# wts_transmitter.net
KiCad netlist of a schematic drawn in EAGLE
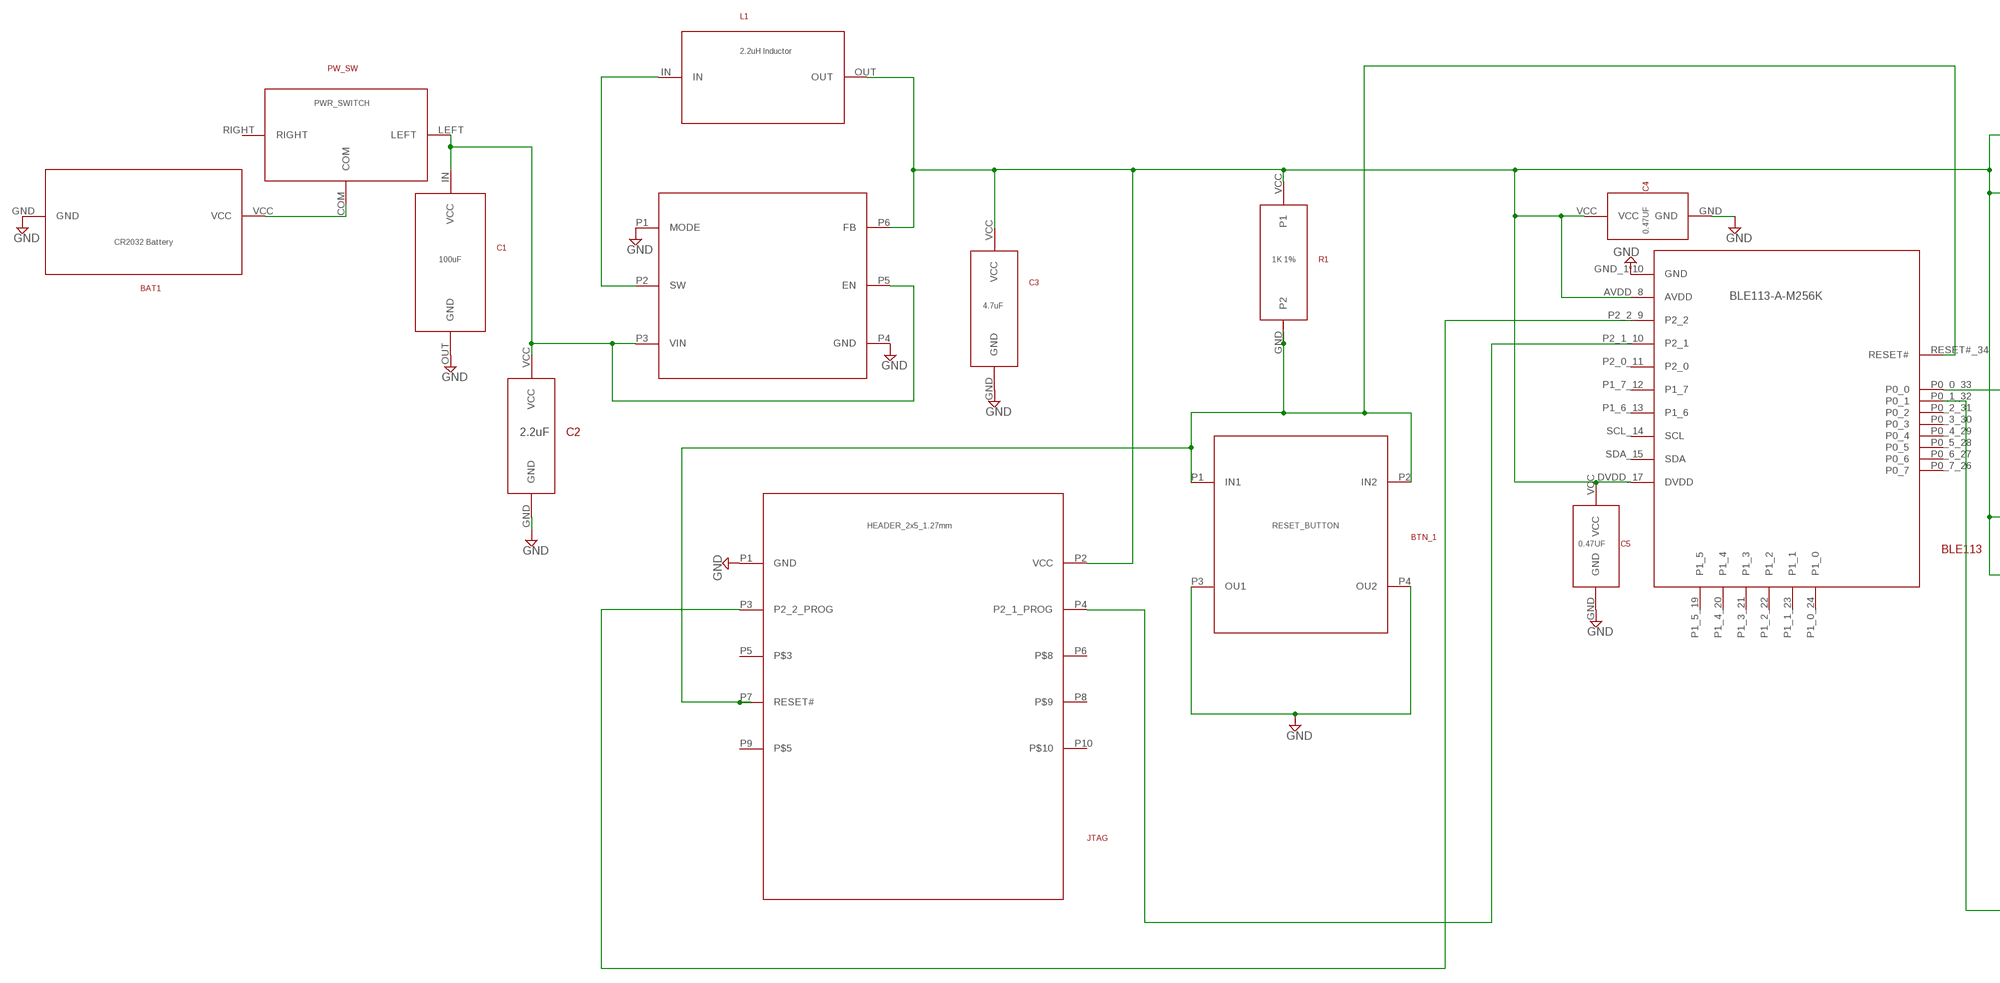
[diagram p0: schematic, sheet 1, part 1 of 2]
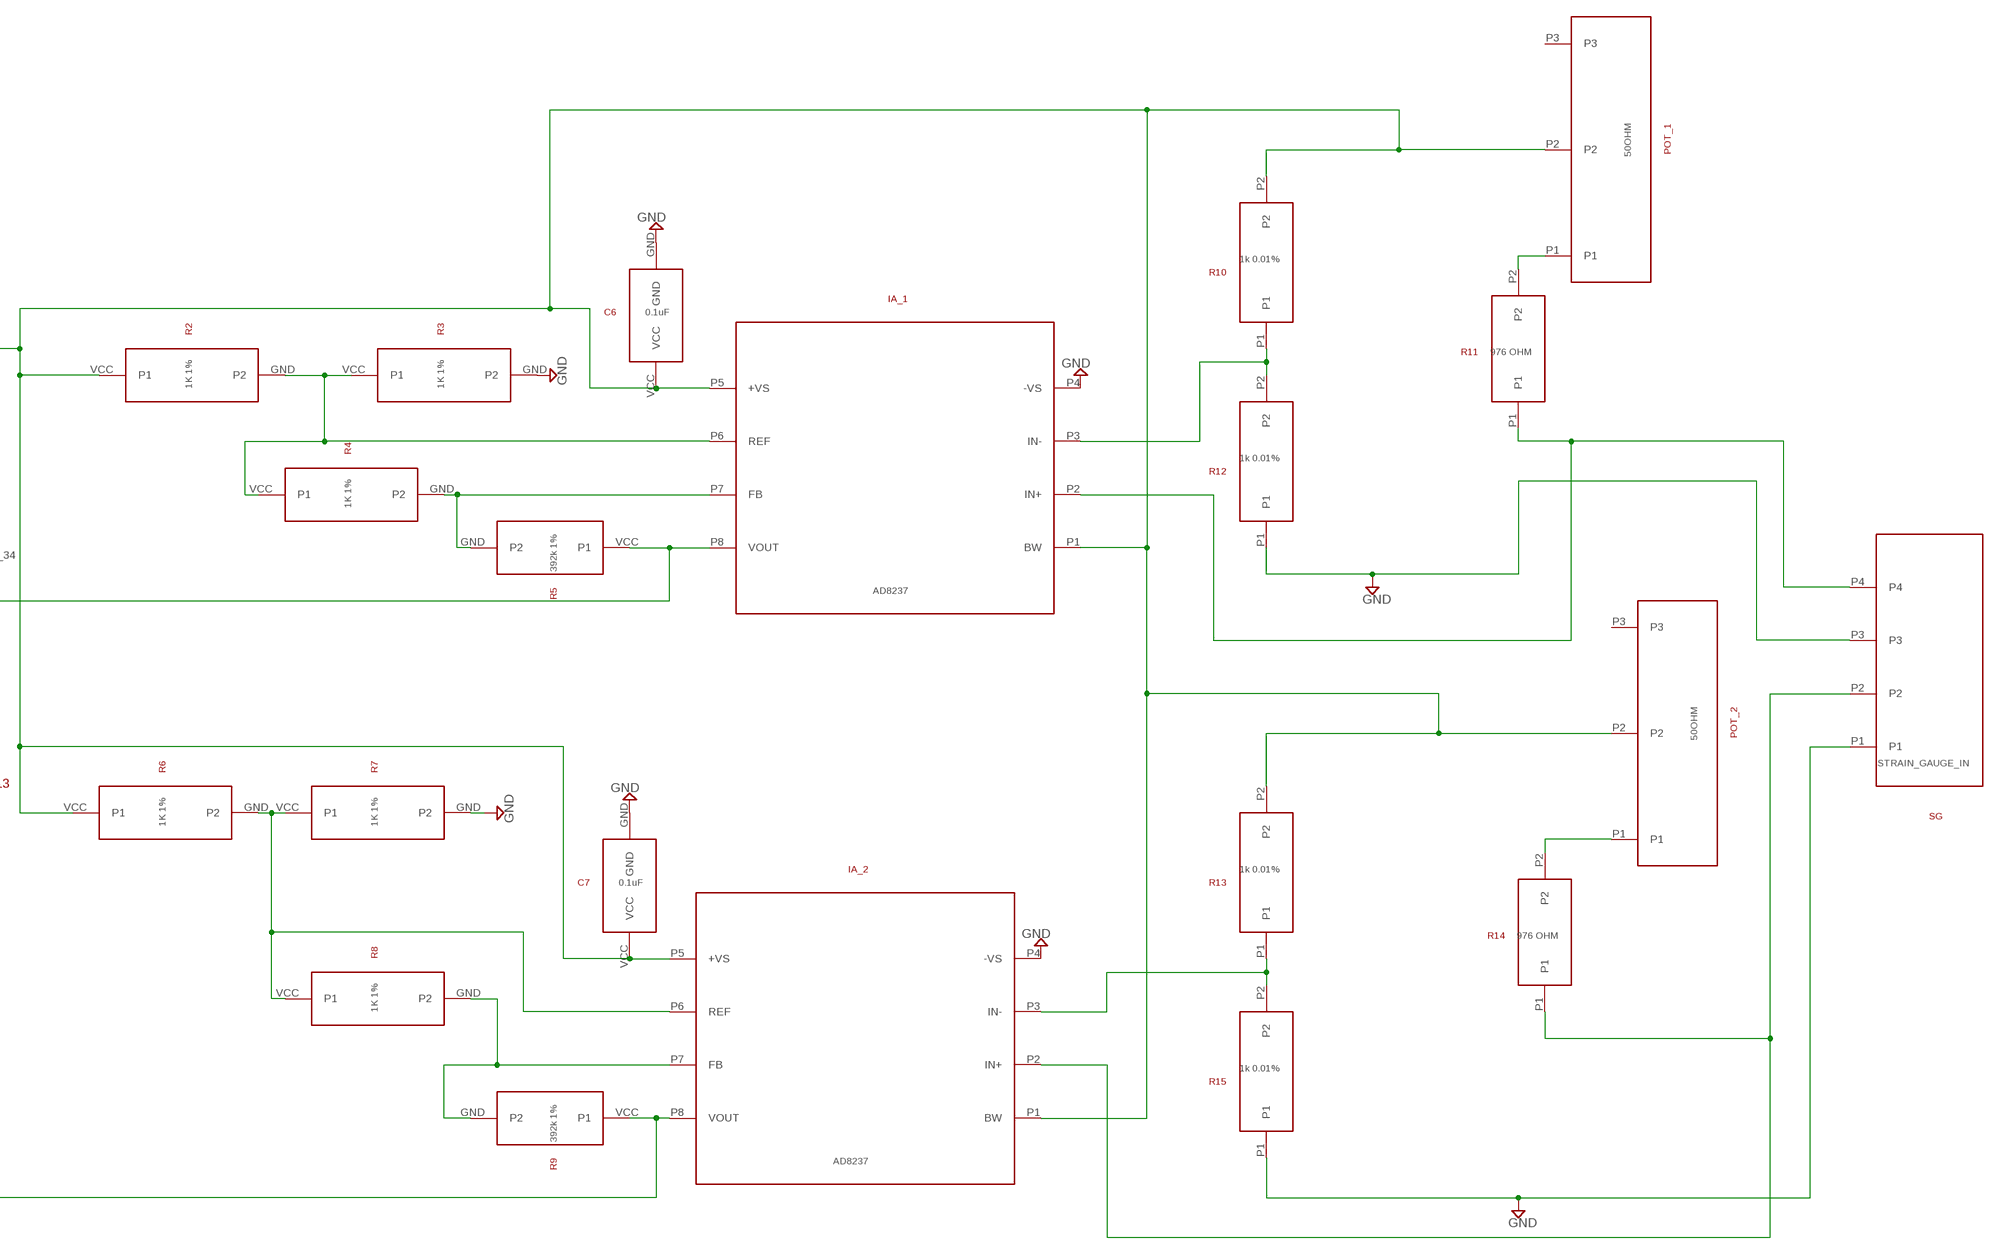
[diagram p1: schematic, sheet 1, part 2 of 2]

(export (version "E")
  (design (tool "Eeschema 10.0.6"))
  (components
    (comp (ref "BAT1")
      (value "CR2032")
      (footprint "eagle-import:CR2032")
      (libsource (lib "eagle-import") (part "CR2032"))
    )
    (comp (ref "BLE113")
      (value "BLE113-A-M256K")
      (footprint "eagle-import:BLE113")
      (libsource (lib "eagle-import") (part "BLE113-A-M256K"))
    )
    (comp (ref "BTN_1")
      (value "RESET_BUTTON")
      (footprint "eagle-import:RESET_SMT")
      (libsource (lib "eagle-import") (part "RESET_BUTTON"))
    )
    (comp (ref "C1")
      (value "100UF_CAP")
      (footprint "eagle-import:1206")
      (libsource (lib "eagle-import") (part "100UF_CAP"))
    )
    (comp (ref "C2")
      (value "2.2UF_CAP")
      (footprint "eagle-import:0603")
      (libsource (lib "eagle-import") (part "2.2UF_CAP"))
    )
    (comp (ref "C3")
      (value "4.7UF_CAP")
      (footprint "eagle-import:0603")
      (libsource (lib "eagle-import") (part "4.7UF_CAP"))
    )
    (comp (ref "C4")
      (value "0.47UF_CAP")
      (footprint "eagle-import:0402")
      (libsource (lib "eagle-import") (part "0.47UF_CAP"))
    )
    (comp (ref "C5")
      (value "0.47UF_CAP")
      (footprint "eagle-import:0402")
      (libsource (lib "eagle-import") (part "0.47UF_CAP"))
    )
    (comp (ref "C6")
      (value "0.1UF_CAP")
      (footprint "eagle-import:0402")
      (libsource (lib "eagle-import") (part "0.1UF_CAP"))
    )
    (comp (ref "C7")
      (value "0.1UF_CAP")
      (footprint "eagle-import:0402")
      (libsource (lib "eagle-import") (part "0.1UF_CAP"))
    )
    (comp (ref "DC_DC")
      (value "TPS62234")
      (footprint "eagle-import:DRY6")
      (libsource (lib "eagle-import") (part "TPS62234"))
    )
    (comp (ref "IA_1")
      (value "AD8237")
      (footprint "eagle-import:MSOP8")
      (libsource (lib "eagle-import") (part "AD8237"))
    )
    (comp (ref "IA_2")
      (value "AD8237")
      (footprint "eagle-import:MSOP8")
      (libsource (lib "eagle-import") (part "AD8237"))
    )
    (comp (ref "JTAG")
      (value "JTAG_HEADER")
      (footprint "eagle-import:1.27MM_2X5_HEADER")
      (libsource (lib "eagle-import") (part "JTAG_HEADER"))
    )
    (comp (ref "L1")
      (value "2.2UH_INDUCTOR")
      (footprint "eagle-import:1206")
      (libsource (lib "eagle-import") (part "2.2UH_INDUCTOR"))
    )
    (comp (ref "POT_1")
      (value "50OHM_TRIMPOT")
      (footprint "eagle-import:PV36W_TRIMPOT")
      (libsource (lib "eagle-import") (part "50OHM_TRIMPOT"))
    )
    (comp (ref "POT_2")
      (value "50OHM_TRIMPOT")
      (footprint "eagle-import:PV36W_TRIMPOT")
      (libsource (lib "eagle-import") (part "50OHM_TRIMPOT"))
    )
    (comp (ref "PW_SW")
      (value "PWR_SWITCH")
      (footprint "eagle-import:PWR_SWITCH")
      (libsource (lib "eagle-import") (part "PWR_SWITCH"))
    )
    (comp (ref "R1")
      (value "1KOHM_RESISTOR_1%")
      (footprint "eagle-import:0603")
      (libsource (lib "eagle-import") (part "1KOHM_RESISTOR_1%"))
    )
    (comp (ref "R2")
      (value "1KOHM_RESISTOR_1%")
      (footprint "eagle-import:0603")
      (libsource (lib "eagle-import") (part "1KOHM_RESISTOR_1%"))
    )
    (comp (ref "R3")
      (value "1KOHM_RESISTOR_1%")
      (footprint "eagle-import:0603")
      (libsource (lib "eagle-import") (part "1KOHM_RESISTOR_1%"))
    )
    (comp (ref "R4")
      (value "1KOHM_RESISTOR_1%")
      (footprint "eagle-import:0603")
      (libsource (lib "eagle-import") (part "1KOHM_RESISTOR_1%"))
    )
    (comp (ref "R5")
      (value "392KOHM_RESISTOR_1%")
      (footprint "eagle-import:0603")
      (libsource (lib "eagle-import") (part "392KOHM_RESISTOR_1%"))
    )
    (comp (ref "R6")
      (value "1KOHM_RESISTOR_1%")
      (footprint "eagle-import:0603")
      (libsource (lib "eagle-import") (part "1KOHM_RESISTOR_1%"))
    )
    (comp (ref "R7")
      (value "1KOHM_RESISTOR_1%")
      (footprint "eagle-import:0603")
      (libsource (lib "eagle-import") (part "1KOHM_RESISTOR_1%"))
    )
    (comp (ref "R8")
      (value "1KOHM_RESISTOR_1%")
      (footprint "eagle-import:0603")
      (libsource (lib "eagle-import") (part "1KOHM_RESISTOR_1%"))
    )
    (comp (ref "R9")
      (value "392KOHM_RESISTOR_1%")
      (footprint "eagle-import:0603")
      (libsource (lib "eagle-import") (part "392KOHM_RESISTOR_1%"))
    )
    (comp (ref "R10")
      (value "1KOHM_RESISTOR_0.01%")
      (footprint "eagle-import:0805")
      (libsource (lib "eagle-import") (part "1KOHM_RESISTOR_0.01%"))
    )
    (comp (ref "R11")
      (value "976OHM_RESISTOR")
      (footprint "eagle-import:0805")
      (libsource (lib "eagle-import") (part "976OHM_RESISTOR"))
    )
    (comp (ref "R12")
      (value "1KOHM_RESISTOR_0.01%")
      (footprint "eagle-import:0805")
      (libsource (lib "eagle-import") (part "1KOHM_RESISTOR_0.01%"))
    )
    (comp (ref "R13")
      (value "1KOHM_RESISTOR_0.01%")
      (footprint "eagle-import:0805")
      (libsource (lib "eagle-import") (part "1KOHM_RESISTOR_0.01%"))
    )
    (comp (ref "R14")
      (value "976OHM_RESISTOR")
      (footprint "eagle-import:0805")
      (libsource (lib "eagle-import") (part "976OHM_RESISTOR"))
    )
    (comp (ref "R15")
      (value "1KOHM_RESISTOR_0.01%")
      (footprint "eagle-import:0805")
      (libsource (lib "eagle-import") (part "1KOHM_RESISTOR_0.01%"))
    )
    (comp (ref "SG")
      (value "4_PIN_5.08MM_TERMINAL")
      (footprint "eagle-import:5.08MM_4PIN_HEADER")
      (libsource (lib "eagle-import") (part "4_PIN_5.08MM_TERMINAL"))
    )
  )
  (nets
    (net (code "1") (name "GND") (class "Default")
      (node (ref "BAT1") (pin "GND") (pinfunction "GND_GND") (pintype "power_in"))
      (node (ref "BLE113") (pin "GND_1") (pinfunction "GND_GND_1") (pintype "power_in"))
      (node (ref "BLE113") (pin "GND_18") (pinfunction "GND_GND_18") (pintype "power_in"))
      (node (ref "BLE113") (pin "GND_2") (pinfunction "GND_GND_2") (pintype "power_in"))
      (node (ref "BLE113") (pin "GND_25") (pinfunction "GND_GND_25") (pintype "power_in"))
      (node (ref "BLE113") (pin "GND_3") (pinfunction "GND_GND_3") (pintype "power_in"))
      (node (ref "BLE113") (pin "GND_36") (pinfunction "GND_GND_36") (pintype "power_in"))
      (node (ref "BLE113") (pin "GND_4") (pinfunction "GND_GND_4") (pintype "power_in"))
      (node (ref "BLE113") (pin "GND_5") (pinfunction "GND_GND_5") (pintype "power_in"))
      (node (ref "BLE113") (pin "GND_6") (pinfunction "GND_GND_6") (pintype "power_in"))
      (node (ref "BLE113") (pin "GND_7") (pinfunction "GND_GND_7") (pintype "power_in"))
      (node (ref "BTN_1") (pin "P3") (pinfunction "OU1_P3") (pintype "bidirectional"))
      (node (ref "BTN_1") (pin "P4") (pinfunction "OU2_P4") (pintype "bidirectional"))
      (node (ref "C1") (pin "OUT") (pinfunction "GND_OUT") (pintype "power_in"))
      (node (ref "C2") (pin "GND") (pinfunction "GND_GND") (pintype "power_in"))
      (node (ref "C3") (pin "GND") (pinfunction "GND_GND") (pintype "bidirectional"))
      (node (ref "C4") (pin "GND") (pinfunction "GND_GND") (pintype "power_in"))
      (node (ref "C5") (pin "GND") (pinfunction "GND_GND") (pintype "power_in"))
      (node (ref "C6") (pin "GND") (pinfunction "GND_GND") (pintype "bidirectional"))
      (node (ref "C7") (pin "GND") (pinfunction "GND_GND") (pintype "bidirectional"))
      (node (ref "DC_DC") (pin "P1") (pinfunction "MODE_P1") (pintype "input"))
      (node (ref "DC_DC") (pin "P4") (pinfunction "GND_P4") (pintype "power_in"))
      (node (ref "IA_1") (pin "P4") (pinfunction "-VS_P4") (pintype "bidirectional"))
      (node (ref "IA_2") (pin "P4") (pinfunction "-VS_P4") (pintype "bidirectional"))
      (node (ref "JTAG") (pin "P1") (pinfunction "GND_P1") (pintype "bidirectional"))
      (node (ref "R12") (pin "P1") (pinfunction "P1_P1") (pintype "bidirectional"))
      (node (ref "R15") (pin "P1") (pinfunction "P1_P1") (pintype "bidirectional"))
      (node (ref "R3") (pin "GND") (pinfunction "P2_GND") (pintype "bidirectional"))
      (node (ref "R7") (pin "GND") (pinfunction "P2_GND") (pintype "bidirectional"))
      (node (ref "SG") (pin "P1") (pinfunction "P1_P1") (pintype "bidirectional"))
      (node (ref "SG") (pin "P3") (pinfunction "P3_P3") (pintype "bidirectional"))
    )
    (net (code "2") (name "Net-(BAT1-PadVCC)") (class "Default")
      (node (ref "BAT1") (pin "VCC") (pinfunction "VCC_VCC") (pintype "power_in"))
      (node (ref "PW_SW") (pin "COM") (pinfunction "COM_COM") (pintype "bidirectional"))
    )
    (net (code "3") (name "Net-(BLE113-AVDD)") (class "Default")
      (node (ref "BLE113") (pin "AVDD_8") (pinfunction "AVDD_AVDD_8") (pintype "power_in"))
      (node (ref "BLE113") (pin "DVDD_17") (pinfunction "DVDD_DVDD_17") (pintype "power_in"))
      (node (ref "C3") (pin "VCC") (pinfunction "VCC_VCC") (pintype "bidirectional"))
      (node (ref "C4") (pin "VCC") (pinfunction "VCC_VCC") (pintype "power_in"))
      (node (ref "C5") (pin "VCC") (pinfunction "VCC_VCC") (pintype "power_in"))
      (node (ref "C6") (pin "VCC") (pinfunction "VCC_VCC") (pintype "bidirectional"))
      (node (ref "C7") (pin "VCC") (pinfunction "VCC_VCC") (pintype "bidirectional"))
      (node (ref "DC_DC") (pin "P6") (pinfunction "FB_P6") (pintype "input"))
      (node (ref "IA_1") (pin "P1") (pinfunction "BW_P1") (pintype "bidirectional"))
      (node (ref "IA_1") (pin "P5") (pinfunction "+VS_P5") (pintype "bidirectional"))
      (node (ref "IA_2") (pin "P1") (pinfunction "BW_P1") (pintype "bidirectional"))
      (node (ref "IA_2") (pin "P5") (pinfunction "+VS_P5") (pintype "bidirectional"))
      (node (ref "JTAG") (pin "P2") (pinfunction "VCC_P2") (pintype "bidirectional"))
      (node (ref "L1") (pin "OUT") (pinfunction "OUT_OUT") (pintype "bidirectional"))
      (node (ref "POT_1") (pin "P2") (pinfunction "P2_P2") (pintype "bidirectional"))
      (node (ref "POT_2") (pin "P2") (pinfunction "P2_P2") (pintype "bidirectional"))
      (node (ref "R1") (pin "VCC") (pinfunction "P1_VCC") (pintype "bidirectional"))
      (node (ref "R10") (pin "P2") (pinfunction "P2_P2") (pintype "bidirectional"))
      (node (ref "R13") (pin "P2") (pinfunction "P2_P2") (pintype "bidirectional"))
      (node (ref "R2") (pin "VCC") (pinfunction "P1_VCC") (pintype "bidirectional"))
      (node (ref "R6") (pin "VCC") (pinfunction "P1_VCC") (pintype "bidirectional"))
    )
    (net (code "4") (name "Net-(BLE113-P0_0)") (class "Default")
      (node (ref "BLE113") (pin "P0_0_33") (pinfunction "P0_0_P0_0_33") (pintype "bidirectional"))
      (node (ref "IA_1") (pin "P8") (pinfunction "VOUT_P8") (pintype "bidirectional"))
      (node (ref "R5") (pin "VCC") (pinfunction "P1_VCC") (pintype "bidirectional"))
    )
    (net (code "5") (name "Net-(BLE113-P0_1)") (class "Default")
      (node (ref "BLE113") (pin "P0_1_32") (pinfunction "P0_1_P0_1_32") (pintype "bidirectional"))
      (node (ref "IA_2") (pin "P8") (pinfunction "VOUT_P8") (pintype "bidirectional"))
      (node (ref "R9") (pin "VCC") (pinfunction "P1_VCC") (pintype "bidirectional"))
    )
    (net (code "6") (name "Net-(BLE113-P2_1)") (class "Default")
      (node (ref "BLE113") (pin "P2_1_10") (pinfunction "P2_1_P2_1_10") (pintype "bidirectional"))
      (node (ref "JTAG") (pin "P4") (pinfunction "P2_1_PROG_P4") (pintype "bidirectional"))
    )
    (net (code "7") (name "Net-(BLE113-P2_2)") (class "Default")
      (node (ref "BLE113") (pin "P2_2_9") (pinfunction "P2_2_P2_2_9") (pintype "bidirectional"))
      (node (ref "JTAG") (pin "P3") (pinfunction "P2_2_PROG_P3") (pintype "bidirectional"))
    )
    (net (code "8") (name "Net-(BLE113-RESET#)") (class "Default")
      (node (ref "BLE113") (pin "RESET#_34") (pinfunction "RESET#_RESET#_34") (pintype "input"))
      (node (ref "BTN_1") (pin "P1") (pinfunction "IN1_P1") (pintype "bidirectional"))
      (node (ref "BTN_1") (pin "P2") (pinfunction "IN2_P2") (pintype "bidirectional"))
      (node (ref "JTAG") (pin "P7") (pinfunction "RESET#_P7") (pintype "bidirectional"))
      (node (ref "R1") (pin "GND") (pinfunction "P2_GND") (pintype "bidirectional"))
    )
    (net (code "9") (name "Net-(C1-VCC)") (class "Default")
      (node (ref "C1") (pin "IN") (pinfunction "VCC_IN") (pintype "power_in"))
      (node (ref "C2") (pin "VCC") (pinfunction "VCC_VCC") (pintype "power_in"))
      (node (ref "DC_DC") (pin "P3") (pinfunction "VIN_P3") (pintype "power_in"))
      (node (ref "DC_DC") (pin "P5") (pinfunction "EN_P5") (pintype "input"))
      (node (ref "PW_SW") (pin "LEFT") (pinfunction "LEFT_LEFT") (pintype "bidirectional"))
    )
    (net (code "10") (name "Net-(DC_DC-SW)") (class "Default")
      (node (ref "DC_DC") (pin "P2") (pinfunction "SW_P2") (pintype "output"))
      (node (ref "L1") (pin "IN") (pinfunction "IN_IN") (pintype "bidirectional"))
    )
    (net (code "11") (name "Net-(IA_1-FB)") (class "Default")
      (node (ref "IA_1") (pin "P7") (pinfunction "FB_P7") (pintype "bidirectional"))
      (node (ref "R4") (pin "GND") (pinfunction "P2_GND") (pintype "bidirectional"))
      (node (ref "R5") (pin "GND") (pinfunction "P2_GND") (pintype "bidirectional"))
    )
    (net (code "12") (name "Net-(IA_1-IN+)") (class "Default")
      (node (ref "IA_1") (pin "P2") (pinfunction "IN+_P2") (pintype "bidirectional"))
      (node (ref "R11") (pin "P1") (pinfunction "P1_P1") (pintype "bidirectional"))
      (node (ref "SG") (pin "P4") (pinfunction "P4_P4") (pintype "bidirectional"))
    )
    (net (code "13") (name "Net-(IA_1-IN-)") (class "Default")
      (node (ref "IA_1") (pin "P3") (pinfunction "IN-_P3") (pintype "bidirectional"))
      (node (ref "R10") (pin "P1") (pinfunction "P1_P1") (pintype "bidirectional"))
      (node (ref "R12") (pin "P2") (pinfunction "P2_P2") (pintype "bidirectional"))
    )
    (net (code "14") (name "Net-(IA_1-REF)") (class "Default")
      (node (ref "IA_1") (pin "P6") (pinfunction "REF_P6") (pintype "bidirectional"))
      (node (ref "R2") (pin "GND") (pinfunction "P2_GND") (pintype "bidirectional"))
      (node (ref "R3") (pin "VCC") (pinfunction "P1_VCC") (pintype "bidirectional"))
      (node (ref "R4") (pin "VCC") (pinfunction "P1_VCC") (pintype "bidirectional"))
    )
    (net (code "15") (name "Net-(IA_2-FB)") (class "Default")
      (node (ref "IA_2") (pin "P7") (pinfunction "FB_P7") (pintype "bidirectional"))
      (node (ref "R8") (pin "GND") (pinfunction "P2_GND") (pintype "bidirectional"))
      (node (ref "R9") (pin "GND") (pinfunction "P2_GND") (pintype "bidirectional"))
    )
    (net (code "16") (name "Net-(IA_2-IN+)") (class "Default")
      (node (ref "IA_2") (pin "P2") (pinfunction "IN+_P2") (pintype "bidirectional"))
      (node (ref "R14") (pin "P1") (pinfunction "P1_P1") (pintype "bidirectional"))
      (node (ref "SG") (pin "P2") (pinfunction "P2_P2") (pintype "bidirectional"))
    )
    (net (code "17") (name "Net-(IA_2-IN-)") (class "Default")
      (node (ref "IA_2") (pin "P3") (pinfunction "IN-_P3") (pintype "bidirectional"))
      (node (ref "R13") (pin "P1") (pinfunction "P1_P1") (pintype "bidirectional"))
      (node (ref "R15") (pin "P2") (pinfunction "P2_P2") (pintype "bidirectional"))
    )
    (net (code "18") (name "Net-(IA_2-REF)") (class "Default")
      (node (ref "IA_2") (pin "P6") (pinfunction "REF_P6") (pintype "bidirectional"))
      (node (ref "R6") (pin "GND") (pinfunction "P2_GND") (pintype "bidirectional"))
      (node (ref "R7") (pin "VCC") (pinfunction "P1_VCC") (pintype "bidirectional"))
      (node (ref "R8") (pin "VCC") (pinfunction "P1_VCC") (pintype "bidirectional"))
    )
    (net (code "19") (name "Net-(POT_1-PadP1)") (class "Default")
      (node (ref "POT_1") (pin "P1") (pinfunction "P1_P1") (pintype "bidirectional"))
      (node (ref "R11") (pin "P2") (pinfunction "P2_P2") (pintype "bidirectional"))
    )
    (net (code "20") (name "Net-(POT_2-PadP1)") (class "Default")
      (node (ref "POT_2") (pin "P1") (pinfunction "P1_P1") (pintype "bidirectional"))
      (node (ref "R14") (pin "P2") (pinfunction "P2_P2") (pintype "bidirectional"))
    )
    (net (code "21") (name "unconnected-(BLE113-P0_2-PadP0_2_31)") (class "Default")
      (node (ref "BLE113") (pin "P0_2_31") (pinfunction "P0_2_P0_2_31") (pintype "bidirectional"))
    )
    (net (code "22") (name "unconnected-(BLE113-P0_3-PadP0_3_30)") (class "Default")
      (node (ref "BLE113") (pin "P0_3_30") (pinfunction "P0_3_P0_3_30") (pintype "bidirectional"))
    )
    (net (code "23") (name "unconnected-(BLE113-P0_4-PadP0_4_29)") (class "Default")
      (node (ref "BLE113") (pin "P0_4_29") (pinfunction "P0_4_P0_4_29") (pintype "bidirectional"))
    )
    (net (code "24") (name "unconnected-(BLE113-P0_5-PadP0_5_28)") (class "Default")
      (node (ref "BLE113") (pin "P0_5_28") (pinfunction "P0_5_P0_5_28") (pintype "bidirectional"))
    )
    (net (code "25") (name "unconnected-(BLE113-P0_6-PadP0_6_27)") (class "Default")
      (node (ref "BLE113") (pin "P0_6_27") (pinfunction "P0_6_P0_6_27") (pintype "bidirectional"))
    )
    (net (code "26") (name "unconnected-(BLE113-P0_7-PadP0_7_26)") (class "Default")
      (node (ref "BLE113") (pin "P0_7_26") (pinfunction "P0_7_P0_7_26") (pintype "bidirectional"))
    )
    (net (code "27") (name "unconnected-(BLE113-P1_0-PadP1_0_24)") (class "Default")
      (node (ref "BLE113") (pin "P1_0_24") (pinfunction "P1_0_P1_0_24") (pintype "bidirectional"))
    )
    (net (code "28") (name "unconnected-(BLE113-P1_1-PadP1_1_23)") (class "Default")
      (node (ref "BLE113") (pin "P1_1_23") (pinfunction "P1_1_P1_1_23") (pintype "bidirectional"))
    )
    (net (code "29") (name "unconnected-(BLE113-P1_2-PadP1_2_22)") (class "Default")
      (node (ref "BLE113") (pin "P1_2_22") (pinfunction "P1_2_P1_2_22") (pintype "bidirectional"))
    )
    (net (code "30") (name "unconnected-(BLE113-P1_3-PadP1_3_21)") (class "Default")
      (node (ref "BLE113") (pin "P1_3_21") (pinfunction "P1_3_P1_3_21") (pintype "bidirectional"))
    )
    (net (code "31") (name "unconnected-(BLE113-P1_4-PadP1_4_20)") (class "Default")
      (node (ref "BLE113") (pin "P1_4_20") (pinfunction "P1_4_P1_4_20") (pintype "bidirectional"))
    )
    (net (code "32") (name "unconnected-(BLE113-P1_5-PadP1_5_19)") (class "Default")
      (node (ref "BLE113") (pin "P1_5_19") (pinfunction "P1_5_P1_5_19") (pintype "bidirectional"))
    )
    (net (code "33") (name "unconnected-(BLE113-P1_6-PadP1_6_13)") (class "Default")
      (node (ref "BLE113") (pin "P1_6_13") (pinfunction "P1_6_P1_6_13") (pintype "bidirectional"))
    )
    (net (code "34") (name "unconnected-(BLE113-P1_7-PadP1_7_12)") (class "Default")
      (node (ref "BLE113") (pin "P1_7_12") (pinfunction "P1_7_P1_7_12") (pintype "bidirectional"))
    )
    (net (code "35") (name "unconnected-(BLE113-P2_0-PadP2_0_11)") (class "Default")
      (node (ref "BLE113") (pin "P2_0_11") (pinfunction "P2_0_P2_0_11") (pintype "bidirectional"))
    )
    (net (code "36") (name "unconnected-(BLE113-SCL-PadSCL_14)") (class "Default")
      (node (ref "BLE113") (pin "SCL_14") (pinfunction "SCL_SCL_14") (pintype "bidirectional"))
    )
    (net (code "37") (name "unconnected-(BLE113-SDA-PadSDA_15)") (class "Default")
      (node (ref "BLE113") (pin "SDA_15") (pinfunction "SDA_SDA_15") (pintype "bidirectional"))
    )
    (net (code "38") (name "unconnected-(JTAG-P$3-PadP5)") (class "Default")
      (node (ref "JTAG") (pin "P5") (pinfunction "P$3_P5") (pintype "bidirectional"))
    )
    (net (code "39") (name "unconnected-(JTAG-P$5-PadP9)") (class "Default")
      (node (ref "JTAG") (pin "P9") (pinfunction "P$5_P9") (pintype "bidirectional"))
    )
    (net (code "40") (name "unconnected-(JTAG-P$8-PadP6)") (class "Default")
      (node (ref "JTAG") (pin "P6") (pinfunction "P$8_P6") (pintype "bidirectional"))
    )
    (net (code "41") (name "unconnected-(JTAG-P$9-PadP8)") (class "Default")
      (node (ref "JTAG") (pin "P8") (pinfunction "P$9_P8") (pintype "bidirectional"))
    )
    (net (code "42") (name "unconnected-(JTAG-P$10-PadP10)") (class "Default")
      (node (ref "JTAG") (pin "P10") (pinfunction "P$10_P10") (pintype "bidirectional"))
    )
    (net (code "43") (name "unconnected-(POT_1-PadP3)") (class "Default")
      (node (ref "POT_1") (pin "P3") (pinfunction "P3_P3") (pintype "bidirectional"))
    )
    (net (code "44") (name "unconnected-(POT_2-PadP3)") (class "Default")
      (node (ref "POT_2") (pin "P3") (pinfunction "P3_P3") (pintype "bidirectional"))
    )
    (net (code "45") (name "unconnected-(PW_SW-PadRIGHT)") (class "Default")
      (node (ref "PW_SW") (pin "RIGHT") (pinfunction "RIGHT_RIGHT") (pintype "bidirectional"))
    )
  )
)
